# Keyboard_Matrix.net
KiCad netlist of a schematic drawn in Altium Designer
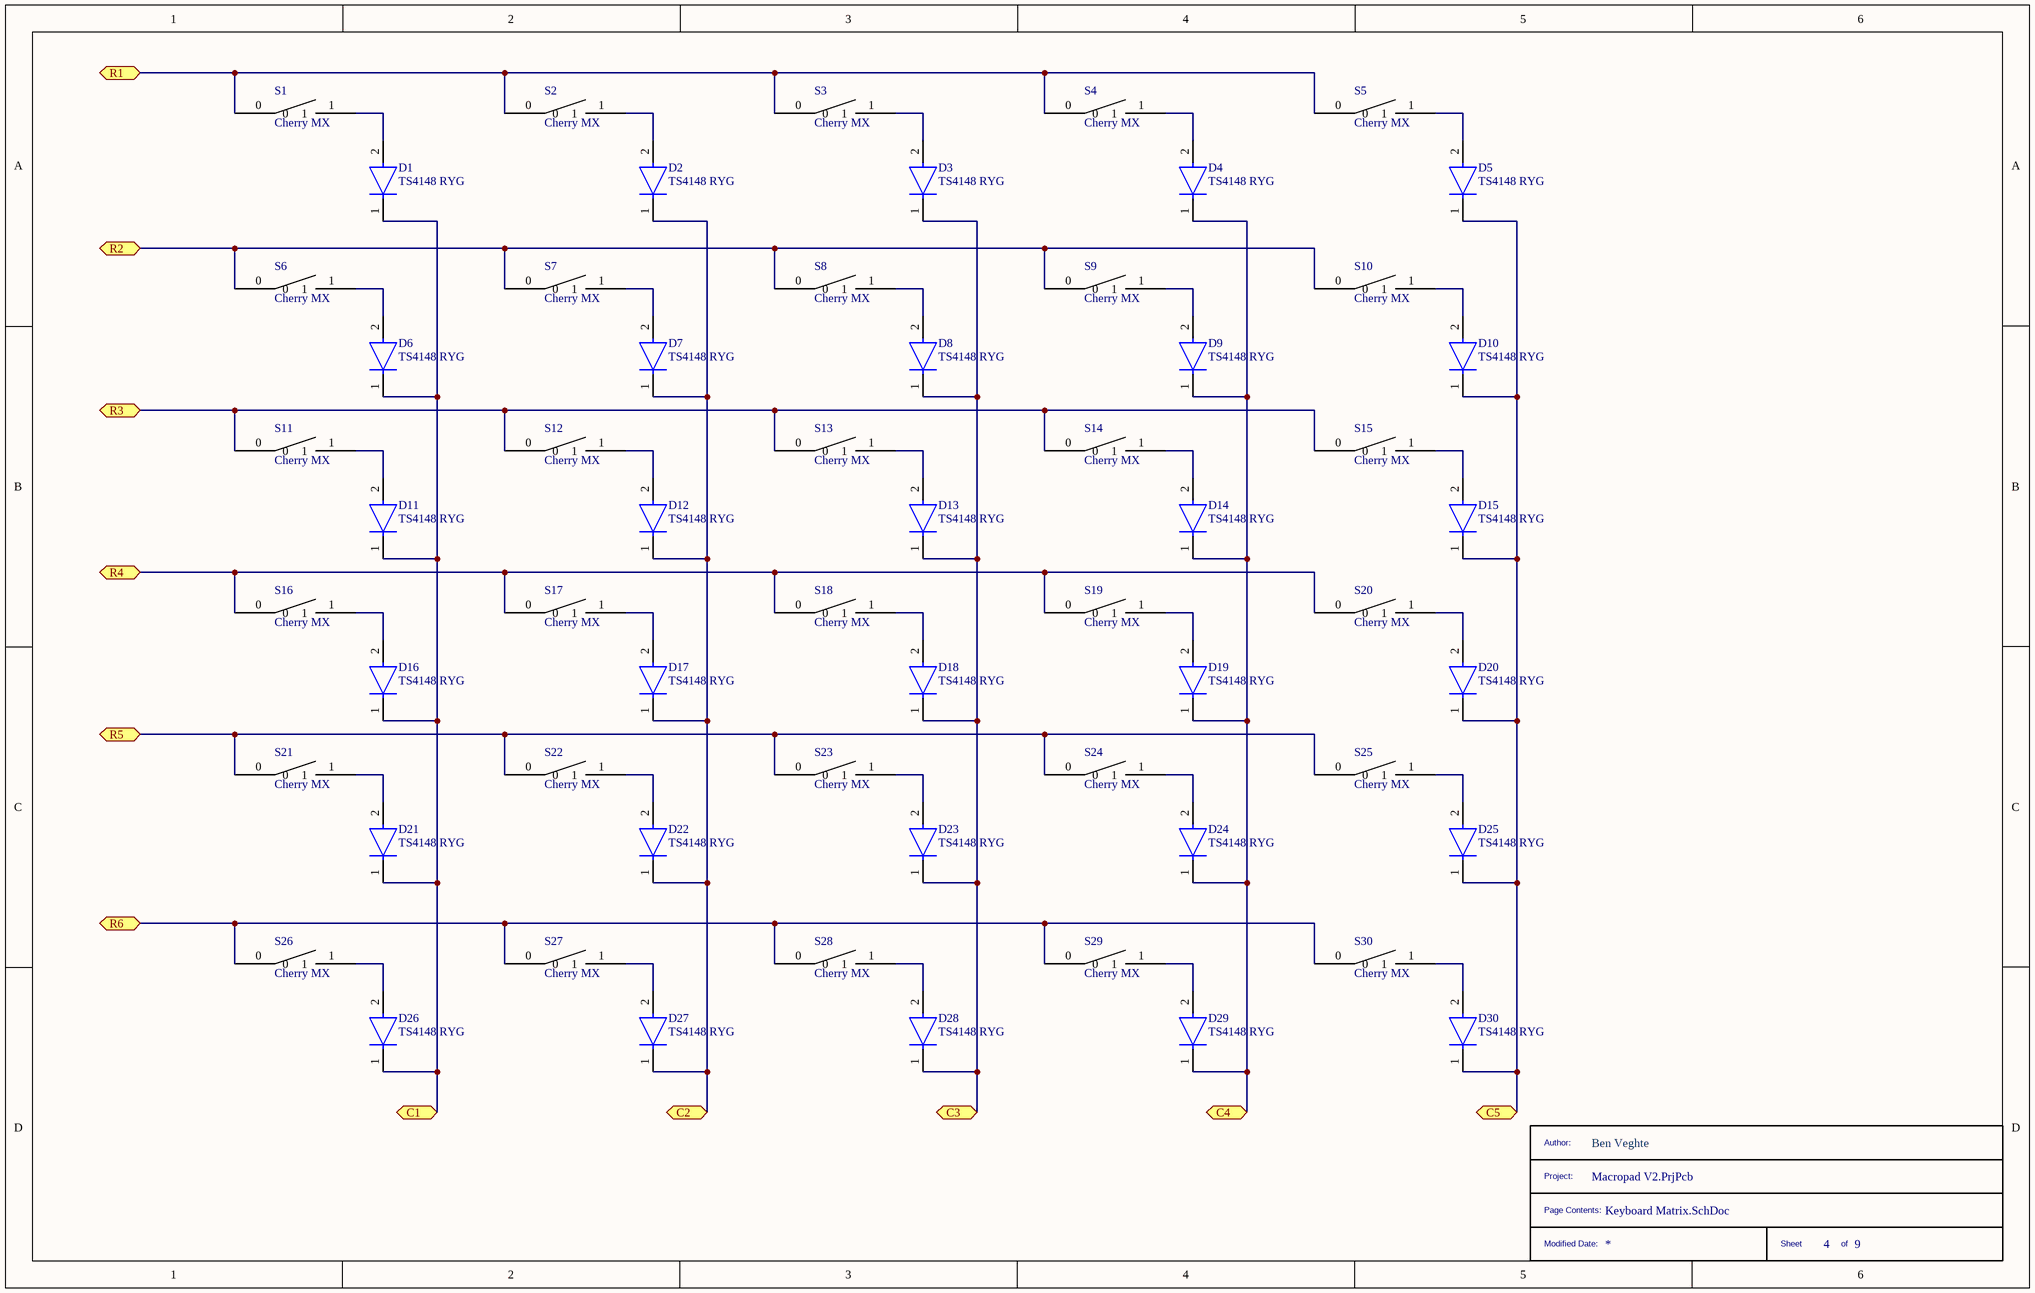
[diagram p0: Keyboard Matrix.SchDoc]

(export (version "E")
  (design (tool "Eeschema 10.0.6"))
  (components
    (comp (ref "D1")
      (value "TS4148 RYG")
      (footprint "FP-TS4148_RYG-MFG")
      (description "Rectifier Diode Switching 75V 0.15A 4ns 2-Pin Case 0805(2012Metric) T/R")
      (libsource (lib "Altium Content Vault") (part "d7152d700b627762746794eb795d46e"))
    )
    (comp (ref "D2")
      (value "TS4148 RYG")
      (footprint "FP-TS4148_RYG-MFG")
      (description "Rectifier Diode Switching 75V 0.15A 4ns 2-Pin Case 0805(2012Metric) T/R")
      (libsource (lib "Altium Content Vault") (part "d7152d700b627762746794eb795d46e"))
    )
    (comp (ref "D3")
      (value "TS4148 RYG")
      (footprint "FP-TS4148_RYG-MFG")
      (description "Rectifier Diode Switching 75V 0.15A 4ns 2-Pin Case 0805(2012Metric) T/R")
      (libsource (lib "Altium Content Vault") (part "d7152d700b627762746794eb795d46e"))
    )
    (comp (ref "D4")
      (value "TS4148 RYG")
      (footprint "FP-TS4148_RYG-MFG")
      (description "Rectifier Diode Switching 75V 0.15A 4ns 2-Pin Case 0805(2012Metric) T/R")
      (libsource (lib "Altium Content Vault") (part "d7152d700b627762746794eb795d46e"))
    )
    (comp (ref "D5")
      (value "TS4148 RYG")
      (footprint "FP-TS4148_RYG-MFG")
      (description "Rectifier Diode Switching 75V 0.15A 4ns 2-Pin Case 0805(2012Metric) T/R")
      (libsource (lib "Altium Content Vault") (part "d7152d700b627762746794eb795d46e"))
    )
    (comp (ref "D6")
      (value "TS4148 RYG")
      (footprint "FP-TS4148_RYG-MFG")
      (description "Rectifier Diode Switching 75V 0.15A 4ns 2-Pin Case 0805(2012Metric) T/R")
      (libsource (lib "Altium Content Vault") (part "d7152d700b627762746794eb795d46e"))
    )
    (comp (ref "D7")
      (value "TS4148 RYG")
      (footprint "FP-TS4148_RYG-MFG")
      (description "Rectifier Diode Switching 75V 0.15A 4ns 2-Pin Case 0805(2012Metric) T/R")
      (libsource (lib "Altium Content Vault") (part "d7152d700b627762746794eb795d46e"))
    )
    (comp (ref "D8")
      (value "TS4148 RYG")
      (footprint "FP-TS4148_RYG-MFG")
      (description "Rectifier Diode Switching 75V 0.15A 4ns 2-Pin Case 0805(2012Metric) T/R")
      (libsource (lib "Altium Content Vault") (part "d7152d700b627762746794eb795d46e"))
    )
    (comp (ref "D9")
      (value "TS4148 RYG")
      (footprint "FP-TS4148_RYG-MFG")
      (description "Rectifier Diode Switching 75V 0.15A 4ns 2-Pin Case 0805(2012Metric) T/R")
      (libsource (lib "Altium Content Vault") (part "d7152d700b627762746794eb795d46e"))
    )
    (comp (ref "D10")
      (value "TS4148 RYG")
      (footprint "FP-TS4148_RYG-MFG")
      (description "Rectifier Diode Switching 75V 0.15A 4ns 2-Pin Case 0805(2012Metric) T/R")
      (libsource (lib "Altium Content Vault") (part "d7152d700b627762746794eb795d46e"))
    )
    (comp (ref "D11")
      (value "TS4148 RYG")
      (footprint "FP-TS4148_RYG-MFG")
      (description "Rectifier Diode Switching 75V 0.15A 4ns 2-Pin Case 0805(2012Metric) T/R")
      (libsource (lib "Altium Content Vault") (part "d7152d700b627762746794eb795d46e"))
    )
    (comp (ref "D12")
      (value "TS4148 RYG")
      (footprint "FP-TS4148_RYG-MFG")
      (description "Rectifier Diode Switching 75V 0.15A 4ns 2-Pin Case 0805(2012Metric) T/R")
      (libsource (lib "Altium Content Vault") (part "d7152d700b627762746794eb795d46e"))
    )
    (comp (ref "D13")
      (value "TS4148 RYG")
      (footprint "FP-TS4148_RYG-MFG")
      (description "Rectifier Diode Switching 75V 0.15A 4ns 2-Pin Case 0805(2012Metric) T/R")
      (libsource (lib "Altium Content Vault") (part "d7152d700b627762746794eb795d46e"))
    )
    (comp (ref "D14")
      (value "TS4148 RYG")
      (footprint "FP-TS4148_RYG-MFG")
      (description "Rectifier Diode Switching 75V 0.15A 4ns 2-Pin Case 0805(2012Metric) T/R")
      (libsource (lib "Altium Content Vault") (part "d7152d700b627762746794eb795d46e"))
    )
    (comp (ref "D15")
      (value "TS4148 RYG")
      (footprint "FP-TS4148_RYG-MFG")
      (description "Rectifier Diode Switching 75V 0.15A 4ns 2-Pin Case 0805(2012Metric) T/R")
      (libsource (lib "Altium Content Vault") (part "d7152d700b627762746794eb795d46e"))
    )
    (comp (ref "D16")
      (value "TS4148 RYG")
      (footprint "FP-TS4148_RYG-MFG")
      (description "Rectifier Diode Switching 75V 0.15A 4ns 2-Pin Case 0805(2012Metric) T/R")
      (libsource (lib "Altium Content Vault") (part "d7152d700b627762746794eb795d46e"))
    )
    (comp (ref "D17")
      (value "TS4148 RYG")
      (footprint "FP-TS4148_RYG-MFG")
      (description "Rectifier Diode Switching 75V 0.15A 4ns 2-Pin Case 0805(2012Metric) T/R")
      (libsource (lib "Altium Content Vault") (part "d7152d700b627762746794eb795d46e"))
    )
    (comp (ref "D18")
      (value "TS4148 RYG")
      (footprint "FP-TS4148_RYG-MFG")
      (description "Rectifier Diode Switching 75V 0.15A 4ns 2-Pin Case 0805(2012Metric) T/R")
      (libsource (lib "Altium Content Vault") (part "d7152d700b627762746794eb795d46e"))
    )
    (comp (ref "D19")
      (value "TS4148 RYG")
      (footprint "FP-TS4148_RYG-MFG")
      (description "Rectifier Diode Switching 75V 0.15A 4ns 2-Pin Case 0805(2012Metric) T/R")
      (libsource (lib "Altium Content Vault") (part "d7152d700b627762746794eb795d46e"))
    )
    (comp (ref "D20")
      (value "TS4148 RYG")
      (footprint "FP-TS4148_RYG-MFG")
      (description "Rectifier Diode Switching 75V 0.15A 4ns 2-Pin Case 0805(2012Metric) T/R")
      (libsource (lib "Altium Content Vault") (part "d7152d700b627762746794eb795d46e"))
    )
    (comp (ref "D21")
      (value "TS4148 RYG")
      (footprint "FP-TS4148_RYG-MFG")
      (description "Rectifier Diode Switching 75V 0.15A 4ns 2-Pin Case 0805(2012Metric) T/R")
      (libsource (lib "Altium Content Vault") (part "d7152d700b627762746794eb795d46e"))
    )
    (comp (ref "D22")
      (value "TS4148 RYG")
      (footprint "FP-TS4148_RYG-MFG")
      (description "Rectifier Diode Switching 75V 0.15A 4ns 2-Pin Case 0805(2012Metric) T/R")
      (libsource (lib "Altium Content Vault") (part "d7152d700b627762746794eb795d46e"))
    )
    (comp (ref "D23")
      (value "TS4148 RYG")
      (footprint "FP-TS4148_RYG-MFG")
      (description "Rectifier Diode Switching 75V 0.15A 4ns 2-Pin Case 0805(2012Metric) T/R")
      (libsource (lib "Altium Content Vault") (part "d7152d700b627762746794eb795d46e"))
    )
    (comp (ref "D24")
      (value "TS4148 RYG")
      (footprint "FP-TS4148_RYG-MFG")
      (description "Rectifier Diode Switching 75V 0.15A 4ns 2-Pin Case 0805(2012Metric) T/R")
      (libsource (lib "Altium Content Vault") (part "d7152d700b627762746794eb795d46e"))
    )
    (comp (ref "D25")
      (value "TS4148 RYG")
      (footprint "FP-TS4148_RYG-MFG")
      (description "Rectifier Diode Switching 75V 0.15A 4ns 2-Pin Case 0805(2012Metric) T/R")
      (libsource (lib "Altium Content Vault") (part "d7152d700b627762746794eb795d46e"))
    )
    (comp (ref "D26")
      (value "TS4148 RYG")
      (footprint "FP-TS4148_RYG-MFG")
      (description "Rectifier Diode Switching 75V 0.15A 4ns 2-Pin Case 0805(2012Metric) T/R")
      (libsource (lib "Altium Content Vault") (part "d7152d700b627762746794eb795d46e"))
    )
    (comp (ref "D27")
      (value "TS4148 RYG")
      (footprint "FP-TS4148_RYG-MFG")
      (description "Rectifier Diode Switching 75V 0.15A 4ns 2-Pin Case 0805(2012Metric) T/R")
      (libsource (lib "Altium Content Vault") (part "d7152d700b627762746794eb795d46e"))
    )
    (comp (ref "D28")
      (value "TS4148 RYG")
      (footprint "FP-TS4148_RYG-MFG")
      (description "Rectifier Diode Switching 75V 0.15A 4ns 2-Pin Case 0805(2012Metric) T/R")
      (libsource (lib "Altium Content Vault") (part "d7152d700b627762746794eb795d46e"))
    )
    (comp (ref "D29")
      (value "TS4148 RYG")
      (footprint "FP-TS4148_RYG-MFG")
      (description "Rectifier Diode Switching 75V 0.15A 4ns 2-Pin Case 0805(2012Metric) T/R")
      (libsource (lib "Altium Content Vault") (part "d7152d700b627762746794eb795d46e"))
    )
    (comp (ref "D30")
      (value "TS4148 RYG")
      (footprint "FP-TS4148_RYG-MFG")
      (description "Rectifier Diode Switching 75V 0.15A 4ns 2-Pin Case 0805(2012Metric) T/R")
      (libsource (lib "Altium Content Vault") (part "d7152d700b627762746794eb795d46e"))
    )
    (comp (ref "S1")
      (value "Cherry MX")
      (footprint "Cherry MX")
      (description "Cherry MX Brown With Fixation Pins")
      (libsource (lib "Universal Parts") (part "Cherry MX"))
    )
    (comp (ref "S2")
      (value "Cherry MX")
      (footprint "Cherry MX")
      (description "Cherry MX Brown With Fixation Pins")
      (libsource (lib "Universal Parts") (part "Cherry MX"))
    )
    (comp (ref "S3")
      (value "Cherry MX")
      (footprint "Cherry MX")
      (description "Cherry MX Brown With Fixation Pins")
      (libsource (lib "Universal Parts") (part "Cherry MX"))
    )
    (comp (ref "S4")
      (value "Cherry MX")
      (footprint "Cherry MX")
      (description "Cherry MX Brown With Fixation Pins")
      (libsource (lib "Universal Parts") (part "Cherry MX"))
    )
    (comp (ref "S5")
      (value "Cherry MX")
      (footprint "Cherry MX")
      (description "Cherry MX Brown With Fixation Pins")
      (libsource (lib "Universal Parts") (part "Cherry MX"))
    )
    (comp (ref "S6")
      (value "Cherry MX")
      (footprint "Cherry MX")
      (description "Cherry MX Brown With Fixation Pins")
      (libsource (lib "Universal Parts") (part "Cherry MX"))
    )
    (comp (ref "S7")
      (value "Cherry MX")
      (footprint "Cherry MX")
      (description "Cherry MX Brown With Fixation Pins")
      (libsource (lib "Universal Parts") (part "Cherry MX"))
    )
    (comp (ref "S8")
      (value "Cherry MX")
      (footprint "Cherry MX")
      (description "Cherry MX Brown With Fixation Pins")
      (libsource (lib "Universal Parts") (part "Cherry MX"))
    )
    (comp (ref "S9")
      (value "Cherry MX")
      (footprint "Cherry MX")
      (description "Cherry MX Brown With Fixation Pins")
      (libsource (lib "Universal Parts") (part "Cherry MX"))
    )
    (comp (ref "S10")
      (value "Cherry MX")
      (footprint "Cherry MX")
      (description "Cherry MX Brown With Fixation Pins")
      (libsource (lib "Universal Parts") (part "Cherry MX"))
    )
    (comp (ref "S11")
      (value "Cherry MX")
      (footprint "Cherry MX")
      (description "Cherry MX Brown With Fixation Pins")
      (libsource (lib "Universal Parts") (part "Cherry MX"))
    )
    (comp (ref "S12")
      (value "Cherry MX")
      (footprint "Cherry MX")
      (description "Cherry MX Brown With Fixation Pins")
      (libsource (lib "Universal Parts") (part "Cherry MX"))
    )
    (comp (ref "S13")
      (value "Cherry MX")
      (footprint "Cherry MX")
      (description "Cherry MX Brown With Fixation Pins")
      (libsource (lib "Universal Parts") (part "Cherry MX"))
    )
    (comp (ref "S14")
      (value "Cherry MX")
      (footprint "Cherry MX")
      (description "Cherry MX Brown With Fixation Pins")
      (libsource (lib "Universal Parts") (part "Cherry MX"))
    )
    (comp (ref "S15")
      (value "Cherry MX")
      (footprint "Cherry MX")
      (description "Cherry MX Brown With Fixation Pins")
      (libsource (lib "Universal Parts") (part "Cherry MX"))
    )
    (comp (ref "S16")
      (value "Cherry MX")
      (footprint "Cherry MX")
      (description "Cherry MX Brown With Fixation Pins")
      (libsource (lib "Universal Parts") (part "Cherry MX"))
    )
    (comp (ref "S17")
      (value "Cherry MX")
      (footprint "Cherry MX")
      (description "Cherry MX Brown With Fixation Pins")
      (libsource (lib "Universal Parts") (part "Cherry MX"))
    )
    (comp (ref "S18")
      (value "Cherry MX")
      (footprint "Cherry MX")
      (description "Cherry MX Brown With Fixation Pins")
      (libsource (lib "Universal Parts") (part "Cherry MX"))
    )
    (comp (ref "S19")
      (value "Cherry MX")
      (footprint "Cherry MX")
      (description "Cherry MX Brown With Fixation Pins")
      (libsource (lib "Universal Parts") (part "Cherry MX"))
    )
    (comp (ref "S20")
      (value "Cherry MX")
      (footprint "Cherry MX")
      (description "Cherry MX Brown With Fixation Pins")
      (libsource (lib "Universal Parts") (part "Cherry MX"))
    )
    (comp (ref "S21")
      (value "Cherry MX")
      (footprint "Cherry MX")
      (description "Cherry MX Brown With Fixation Pins")
      (libsource (lib "Universal Parts") (part "Cherry MX"))
    )
    (comp (ref "S22")
      (value "Cherry MX")
      (footprint "Cherry MX")
      (description "Cherry MX Brown With Fixation Pins")
      (libsource (lib "Universal Parts") (part "Cherry MX"))
    )
    (comp (ref "S23")
      (value "Cherry MX")
      (footprint "Cherry MX")
      (description "Cherry MX Brown With Fixation Pins")
      (libsource (lib "Universal Parts") (part "Cherry MX"))
    )
    (comp (ref "S24")
      (value "Cherry MX")
      (footprint "Cherry MX")
      (description "Cherry MX Brown With Fixation Pins")
      (libsource (lib "Universal Parts") (part "Cherry MX"))
    )
    (comp (ref "S25")
      (value "Cherry MX")
      (footprint "Cherry MX")
      (description "Cherry MX Brown With Fixation Pins")
      (libsource (lib "Universal Parts") (part "Cherry MX"))
    )
    (comp (ref "S26")
      (value "Cherry MX")
      (footprint "Cherry MX")
      (description "Cherry MX Brown With Fixation Pins")
      (libsource (lib "Universal Parts") (part "Cherry MX"))
    )
    (comp (ref "S27")
      (value "Cherry MX")
      (footprint "Cherry MX")
      (description "Cherry MX Brown With Fixation Pins")
      (libsource (lib "Universal Parts") (part "Cherry MX"))
    )
    (comp (ref "S28")
      (value "Cherry MX")
      (footprint "Cherry MX")
      (description "Cherry MX Brown With Fixation Pins")
      (libsource (lib "Universal Parts") (part "Cherry MX"))
    )
    (comp (ref "S29")
      (value "Cherry MX")
      (footprint "Cherry MX")
      (description "Cherry MX Brown With Fixation Pins")
      (libsource (lib "Universal Parts") (part "Cherry MX"))
    )
    (comp (ref "S30")
      (value "Cherry MX")
      (footprint "Cherry MX")
      (description "Cherry MX Brown With Fixation Pins")
      (libsource (lib "Universal Parts") (part "Cherry MX"))
    )
  )
  (nets
    (net (code "1") (name "/C1") (class "Default")
      (node (ref "D1") (pin "1") (pinfunction "C_1") (pintype "passive"))
      (node (ref "D11") (pin "1") (pinfunction "C_1") (pintype "passive"))
      (node (ref "D16") (pin "1") (pinfunction "C_1") (pintype "passive"))
      (node (ref "D21") (pin "1") (pinfunction "C_1") (pintype "passive"))
      (node (ref "D26") (pin "1") (pinfunction "C_1") (pintype "passive"))
      (node (ref "D6") (pin "1") (pinfunction "C_1") (pintype "passive"))
    )
    (net (code "2") (name "/C2") (class "Default")
      (node (ref "D12") (pin "1") (pinfunction "C_1") (pintype "passive"))
      (node (ref "D17") (pin "1") (pinfunction "C_1") (pintype "passive"))
      (node (ref "D2") (pin "1") (pinfunction "C_1") (pintype "passive"))
      (node (ref "D22") (pin "1") (pinfunction "C_1") (pintype "passive"))
      (node (ref "D27") (pin "1") (pinfunction "C_1") (pintype "passive"))
      (node (ref "D7") (pin "1") (pinfunction "C_1") (pintype "passive"))
    )
    (net (code "3") (name "/C3") (class "Default")
      (node (ref "D13") (pin "1") (pinfunction "C_1") (pintype "passive"))
      (node (ref "D18") (pin "1") (pinfunction "C_1") (pintype "passive"))
      (node (ref "D23") (pin "1") (pinfunction "C_1") (pintype "passive"))
      (node (ref "D28") (pin "1") (pinfunction "C_1") (pintype "passive"))
      (node (ref "D3") (pin "1") (pinfunction "C_1") (pintype "passive"))
      (node (ref "D8") (pin "1") (pinfunction "C_1") (pintype "passive"))
    )
    (net (code "4") (name "/C4") (class "Default")
      (node (ref "D14") (pin "1") (pinfunction "C_1") (pintype "passive"))
      (node (ref "D19") (pin "1") (pinfunction "C_1") (pintype "passive"))
      (node (ref "D24") (pin "1") (pinfunction "C_1") (pintype "passive"))
      (node (ref "D29") (pin "1") (pinfunction "C_1") (pintype "passive"))
      (node (ref "D4") (pin "1") (pinfunction "C_1") (pintype "passive"))
      (node (ref "D9") (pin "1") (pinfunction "C_1") (pintype "passive"))
    )
    (net (code "5") (name "/C5") (class "Default")
      (node (ref "D10") (pin "1") (pinfunction "C_1") (pintype "passive"))
      (node (ref "D15") (pin "1") (pinfunction "C_1") (pintype "passive"))
      (node (ref "D20") (pin "1") (pinfunction "C_1") (pintype "passive"))
      (node (ref "D25") (pin "1") (pinfunction "C_1") (pintype "passive"))
      (node (ref "D30") (pin "1") (pinfunction "C_1") (pintype "passive"))
      (node (ref "D5") (pin "1") (pinfunction "C_1") (pintype "passive"))
    )
    (net (code "6") (name "/R1") (class "Default")
      (node (ref "S1") (pin "0") (pinfunction "0_0") (pintype "passive"))
      (node (ref "S2") (pin "0") (pinfunction "0_0") (pintype "passive"))
      (node (ref "S3") (pin "0") (pinfunction "0_0") (pintype "passive"))
      (node (ref "S4") (pin "0") (pinfunction "0_0") (pintype "passive"))
      (node (ref "S5") (pin "0") (pinfunction "0_0") (pintype "passive"))
    )
    (net (code "7") (name "/R2") (class "Default")
      (node (ref "S10") (pin "0") (pinfunction "0_0") (pintype "passive"))
      (node (ref "S6") (pin "0") (pinfunction "0_0") (pintype "passive"))
      (node (ref "S7") (pin "0") (pinfunction "0_0") (pintype "passive"))
      (node (ref "S8") (pin "0") (pinfunction "0_0") (pintype "passive"))
      (node (ref "S9") (pin "0") (pinfunction "0_0") (pintype "passive"))
    )
    (net (code "8") (name "/R3") (class "Default")
      (node (ref "S11") (pin "0") (pinfunction "0_0") (pintype "passive"))
      (node (ref "S12") (pin "0") (pinfunction "0_0") (pintype "passive"))
      (node (ref "S13") (pin "0") (pinfunction "0_0") (pintype "passive"))
      (node (ref "S14") (pin "0") (pinfunction "0_0") (pintype "passive"))
      (node (ref "S15") (pin "0") (pinfunction "0_0") (pintype "passive"))
    )
    (net (code "9") (name "/R4") (class "Default")
      (node (ref "S16") (pin "0") (pinfunction "0_0") (pintype "passive"))
      (node (ref "S17") (pin "0") (pinfunction "0_0") (pintype "passive"))
      (node (ref "S18") (pin "0") (pinfunction "0_0") (pintype "passive"))
      (node (ref "S19") (pin "0") (pinfunction "0_0") (pintype "passive"))
      (node (ref "S20") (pin "0") (pinfunction "0_0") (pintype "passive"))
    )
    (net (code "10") (name "/R5") (class "Default")
      (node (ref "S21") (pin "0") (pinfunction "0_0") (pintype "passive"))
      (node (ref "S22") (pin "0") (pinfunction "0_0") (pintype "passive"))
      (node (ref "S23") (pin "0") (pinfunction "0_0") (pintype "passive"))
      (node (ref "S24") (pin "0") (pinfunction "0_0") (pintype "passive"))
      (node (ref "S25") (pin "0") (pinfunction "0_0") (pintype "passive"))
    )
    (net (code "11") (name "/R6") (class "Default")
      (node (ref "S26") (pin "0") (pinfunction "0_0") (pintype "passive"))
      (node (ref "S27") (pin "0") (pinfunction "0_0") (pintype "passive"))
      (node (ref "S28") (pin "0") (pinfunction "0_0") (pintype "passive"))
      (node (ref "S29") (pin "0") (pinfunction "0_0") (pintype "passive"))
      (node (ref "S30") (pin "0") (pinfunction "0_0") (pintype "passive"))
    )
    (net (code "12") (name "Net-(D1-A)") (class "Default")
      (node (ref "D1") (pin "2") (pinfunction "A_2") (pintype "passive"))
      (node (ref "S1") (pin "1") (pinfunction "1_1") (pintype "passive"))
    )
    (net (code "13") (name "Net-(D2-A)") (class "Default")
      (node (ref "D2") (pin "2") (pinfunction "A_2") (pintype "passive"))
      (node (ref "S2") (pin "1") (pinfunction "1_1") (pintype "passive"))
    )
    (net (code "14") (name "Net-(D3-A)") (class "Default")
      (node (ref "D3") (pin "2") (pinfunction "A_2") (pintype "passive"))
      (node (ref "S3") (pin "1") (pinfunction "1_1") (pintype "passive"))
    )
    (net (code "15") (name "Net-(D4-A)") (class "Default")
      (node (ref "D4") (pin "2") (pinfunction "A_2") (pintype "passive"))
      (node (ref "S4") (pin "1") (pinfunction "1_1") (pintype "passive"))
    )
    (net (code "16") (name "Net-(D5-A)") (class "Default")
      (node (ref "D5") (pin "2") (pinfunction "A_2") (pintype "passive"))
      (node (ref "S5") (pin "1") (pinfunction "1_1") (pintype "passive"))
    )
    (net (code "17") (name "Net-(D6-A)") (class "Default")
      (node (ref "D6") (pin "2") (pinfunction "A_2") (pintype "passive"))
      (node (ref "S6") (pin "1") (pinfunction "1_1") (pintype "passive"))
    )
    (net (code "18") (name "Net-(D7-A)") (class "Default")
      (node (ref "D7") (pin "2") (pinfunction "A_2") (pintype "passive"))
      (node (ref "S7") (pin "1") (pinfunction "1_1") (pintype "passive"))
    )
    (net (code "19") (name "Net-(D8-A)") (class "Default")
      (node (ref "D8") (pin "2") (pinfunction "A_2") (pintype "passive"))
      (node (ref "S8") (pin "1") (pinfunction "1_1") (pintype "passive"))
    )
    (net (code "20") (name "Net-(D9-A)") (class "Default")
      (node (ref "D9") (pin "2") (pinfunction "A_2") (pintype "passive"))
      (node (ref "S9") (pin "1") (pinfunction "1_1") (pintype "passive"))
    )
    (net (code "21") (name "Net-(D10-A)") (class "Default")
      (node (ref "D10") (pin "2") (pinfunction "A_2") (pintype "passive"))
      (node (ref "S10") (pin "1") (pinfunction "1_1") (pintype "passive"))
    )
    (net (code "22") (name "Net-(D11-A)") (class "Default")
      (node (ref "D11") (pin "2") (pinfunction "A_2") (pintype "passive"))
      (node (ref "S11") (pin "1") (pinfunction "1_1") (pintype "passive"))
    )
    (net (code "23") (name "Net-(D12-A)") (class "Default")
      (node (ref "D12") (pin "2") (pinfunction "A_2") (pintype "passive"))
      (node (ref "S12") (pin "1") (pinfunction "1_1") (pintype "passive"))
    )
    (net (code "24") (name "Net-(D13-A)") (class "Default")
      (node (ref "D13") (pin "2") (pinfunction "A_2") (pintype "passive"))
      (node (ref "S13") (pin "1") (pinfunction "1_1") (pintype "passive"))
    )
    (net (code "25") (name "Net-(D14-A)") (class "Default")
      (node (ref "D14") (pin "2") (pinfunction "A_2") (pintype "passive"))
      (node (ref "S14") (pin "1") (pinfunction "1_1") (pintype "passive"))
    )
    (net (code "26") (name "Net-(D15-A)") (class "Default")
      (node (ref "D15") (pin "2") (pinfunction "A_2") (pintype "passive"))
      (node (ref "S15") (pin "1") (pinfunction "1_1") (pintype "passive"))
    )
    (net (code "27") (name "Net-(D16-A)") (class "Default")
      (node (ref "D16") (pin "2") (pinfunction "A_2") (pintype "passive"))
      (node (ref "S16") (pin "1") (pinfunction "1_1") (pintype "passive"))
    )
    (net (code "28") (name "Net-(D17-A)") (class "Default")
      (node (ref "D17") (pin "2") (pinfunction "A_2") (pintype "passive"))
      (node (ref "S17") (pin "1") (pinfunction "1_1") (pintype "passive"))
    )
    (net (code "29") (name "Net-(D18-A)") (class "Default")
      (node (ref "D18") (pin "2") (pinfunction "A_2") (pintype "passive"))
      (node (ref "S18") (pin "1") (pinfunction "1_1") (pintype "passive"))
    )
    (net (code "30") (name "Net-(D19-A)") (class "Default")
      (node (ref "D19") (pin "2") (pinfunction "A_2") (pintype "passive"))
      (node (ref "S19") (pin "1") (pinfunction "1_1") (pintype "passive"))
    )
    (net (code "31") (name "Net-(D20-A)") (class "Default")
      (node (ref "D20") (pin "2") (pinfunction "A_2") (pintype "passive"))
      (node (ref "S20") (pin "1") (pinfunction "1_1") (pintype "passive"))
    )
    (net (code "32") (name "Net-(D21-A)") (class "Default")
      (node (ref "D21") (pin "2") (pinfunction "A_2") (pintype "passive"))
      (node (ref "S21") (pin "1") (pinfunction "1_1") (pintype "passive"))
    )
    (net (code "33") (name "Net-(D22-A)") (class "Default")
      (node (ref "D22") (pin "2") (pinfunction "A_2") (pintype "passive"))
      (node (ref "S22") (pin "1") (pinfunction "1_1") (pintype "passive"))
    )
    (net (code "34") (name "Net-(D23-A)") (class "Default")
      (node (ref "D23") (pin "2") (pinfunction "A_2") (pintype "passive"))
      (node (ref "S23") (pin "1") (pinfunction "1_1") (pintype "passive"))
    )
    (net (code "35") (name "Net-(D24-A)") (class "Default")
      (node (ref "D24") (pin "2") (pinfunction "A_2") (pintype "passive"))
      (node (ref "S24") (pin "1") (pinfunction "1_1") (pintype "passive"))
    )
    (net (code "36") (name "Net-(D25-A)") (class "Default")
      (node (ref "D25") (pin "2") (pinfunction "A_2") (pintype "passive"))
      (node (ref "S25") (pin "1") (pinfunction "1_1") (pintype "passive"))
    )
    (net (code "37") (name "Net-(D26-A)") (class "Default")
      (node (ref "D26") (pin "2") (pinfunction "A_2") (pintype "passive"))
      (node (ref "S26") (pin "1") (pinfunction "1_1") (pintype "passive"))
    )
    (net (code "38") (name "Net-(D27-A)") (class "Default")
      (node (ref "D27") (pin "2") (pinfunction "A_2") (pintype "passive"))
      (node (ref "S27") (pin "1") (pinfunction "1_1") (pintype "passive"))
    )
    (net (code "39") (name "Net-(D28-A)") (class "Default")
      (node (ref "D28") (pin "2") (pinfunction "A_2") (pintype "passive"))
      (node (ref "S28") (pin "1") (pinfunction "1_1") (pintype "passive"))
    )
    (net (code "40") (name "Net-(D29-A)") (class "Default")
      (node (ref "D29") (pin "2") (pinfunction "A_2") (pintype "passive"))
      (node (ref "S29") (pin "1") (pinfunction "1_1") (pintype "passive"))
    )
    (net (code "41") (name "Net-(D30-A)") (class "Default")
      (node (ref "D30") (pin "2") (pinfunction "A_2") (pintype "passive"))
      (node (ref "S30") (pin "1") (pinfunction "1_1") (pintype "passive"))
    )
  )
)
